# SCH_Senior_Transmitter_2026-04-05.net
KiCad netlist of a schematic drawn in EasyEDA
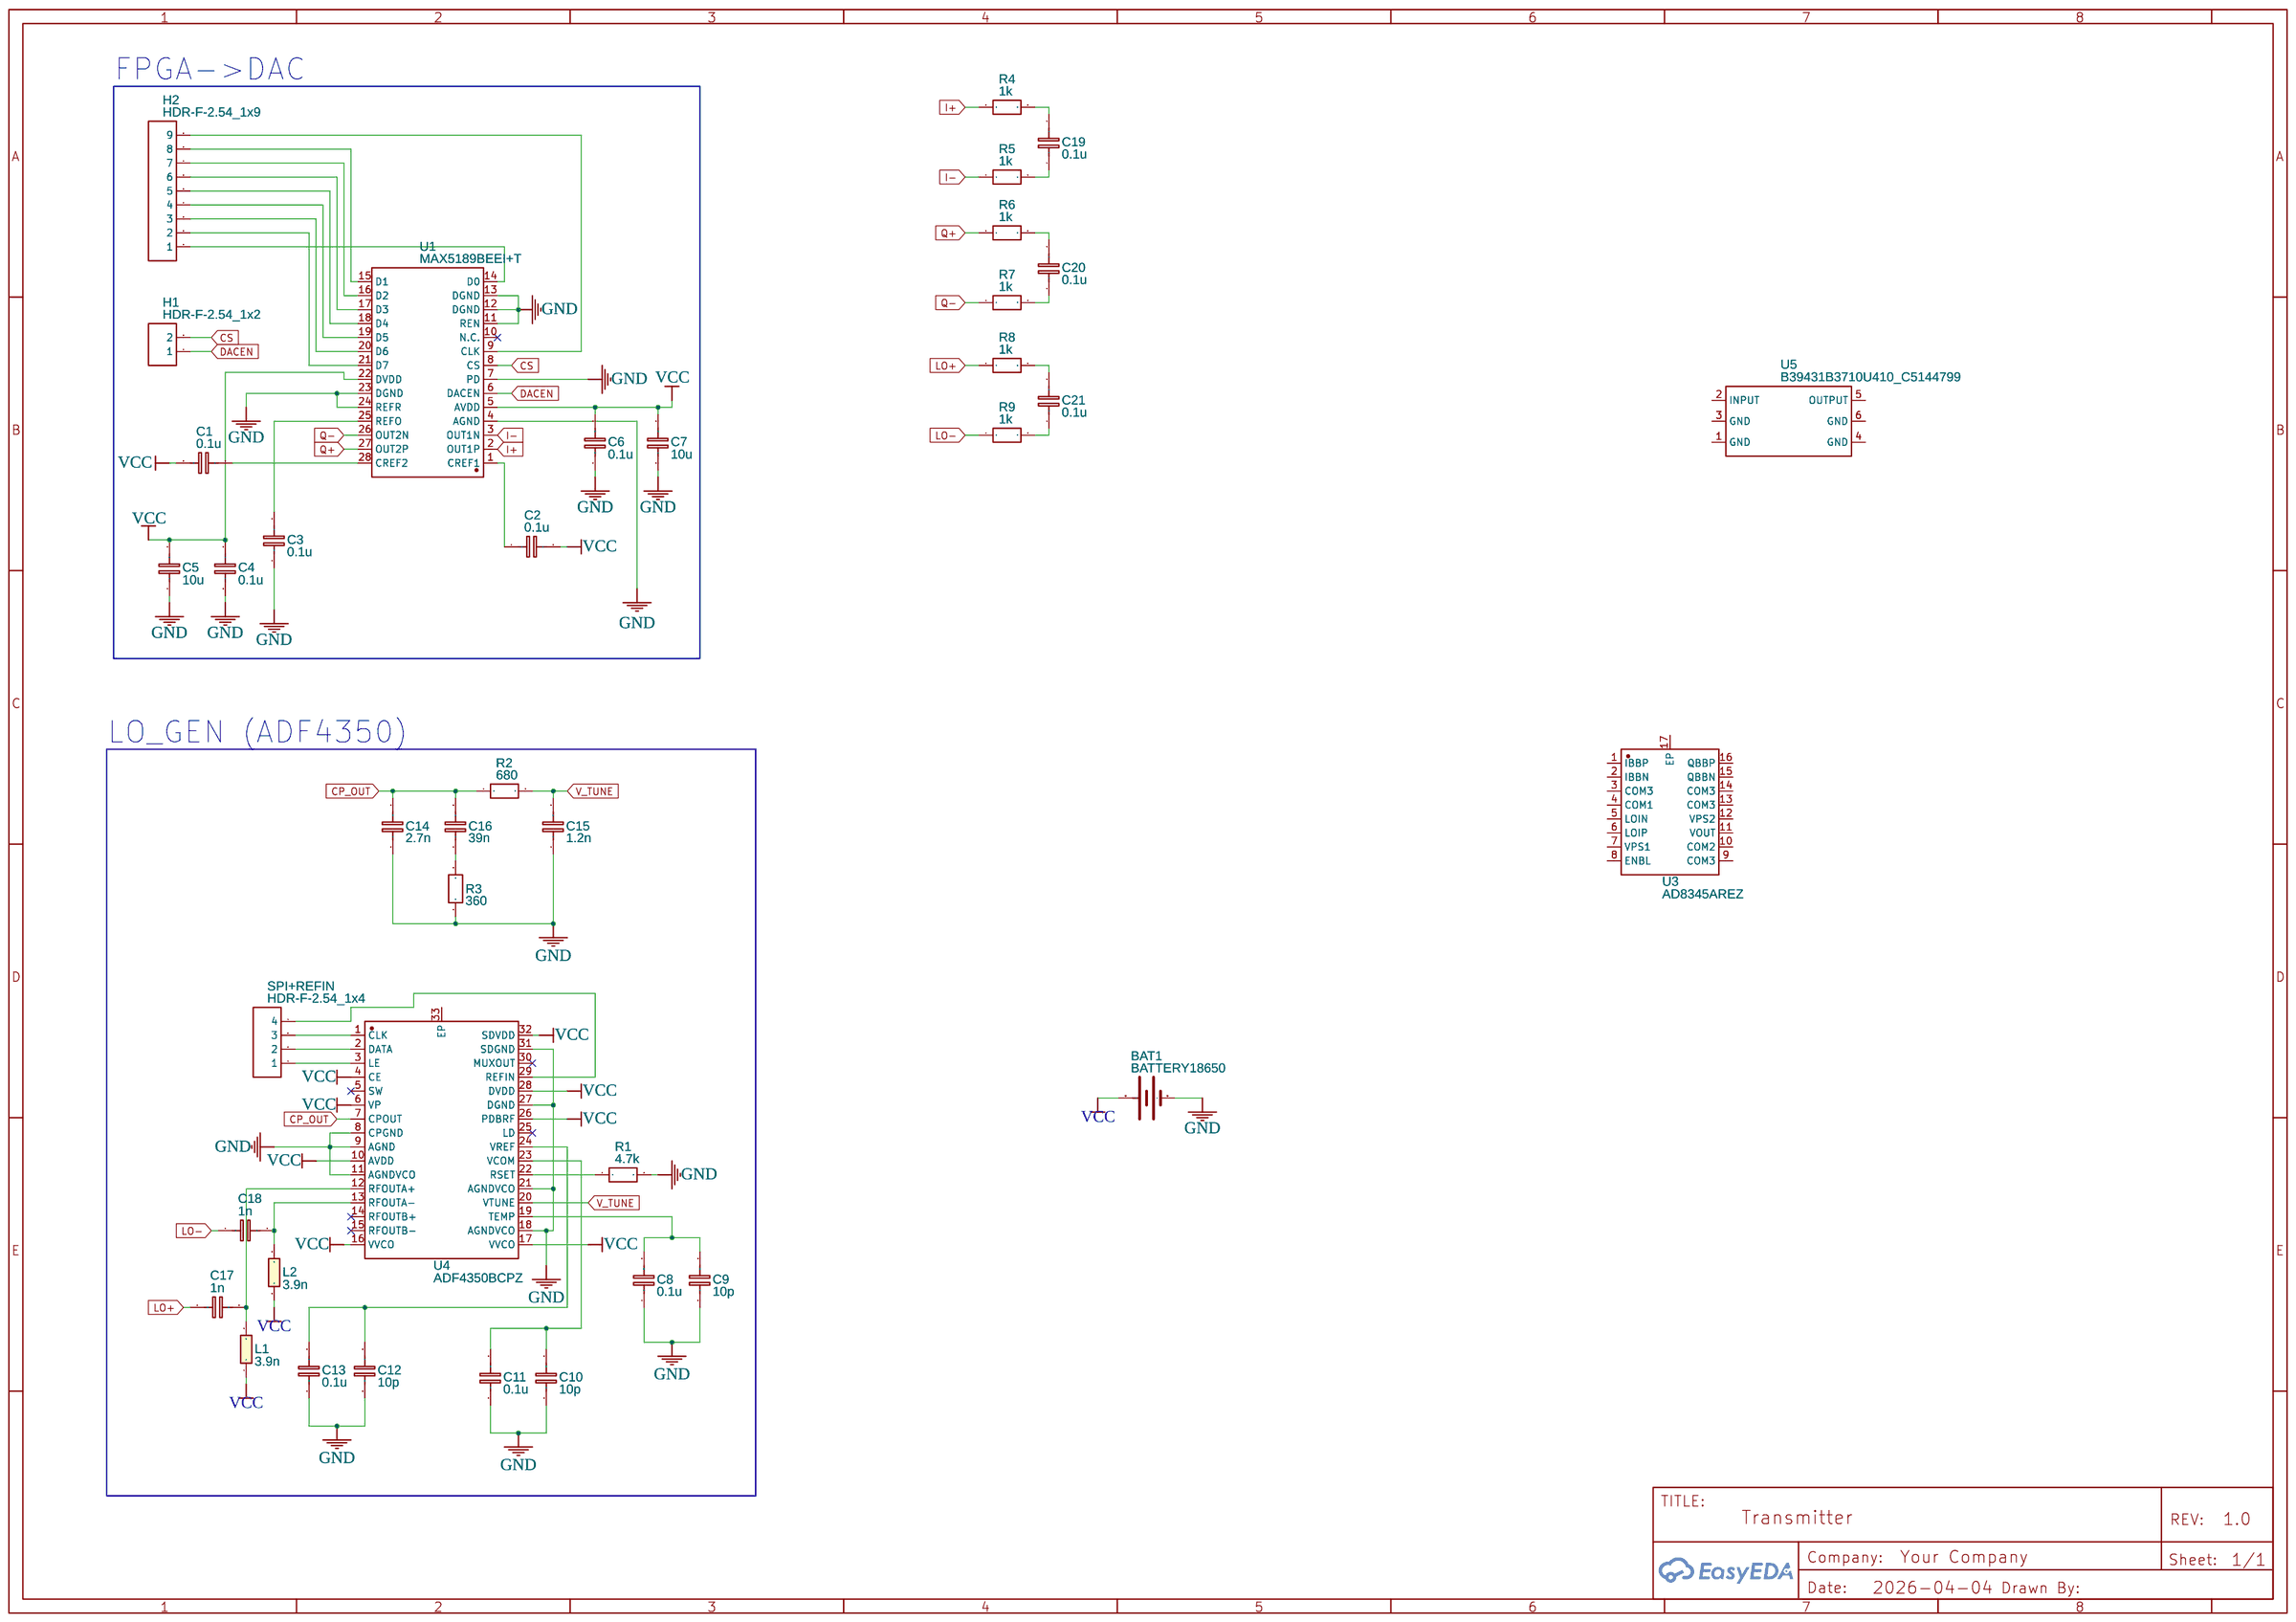
[diagram p0: schematic sheet]

(export (version "E")
  (design (tool "Eeschema 10.0.6"))
  (components
    (comp (ref "BAT1") (value "BATTERY18650") (libsource (lib "") (part "BATTERY18650")))
    (comp (ref "C1") (value "0.1u") (libsource (lib "") (part "C_0603_EU_3")))
    (comp (ref "C2") (value "0.1u") (libsource (lib "") (part "C_0603_EU_3")))
    (comp (ref "C3") (value "0.1u") (libsource (lib "") (part "C_0603_EU")))
    (comp (ref "C4") (value "0.1u") (libsource (lib "") (part "C_0603_EU")))
    (comp (ref "C5") (value "10u") (libsource (lib "") (part "C_0603_EU")))
    (comp (ref "C6") (value "0.1u") (libsource (lib "") (part "C_0603_EU_2")))
    (comp (ref "C7") (value "10u") (libsource (lib "") (part "C_0603_EU_2")))
    (comp (ref "C8") (value "0.1u") (libsource (lib "") (part "C_0603_EU_1")))
    (comp (ref "C9") (value "10p") (libsource (lib "") (part "C_0603_EU_1")))
    (comp (ref "C10") (value "10p") (libsource (lib "") (part "C_0603_EU_2")))
    (comp (ref "C11") (value "0.1u") (libsource (lib "") (part "C_0603_EU_2")))
    (comp (ref "C12") (value "10p") (libsource (lib "") (part "C_0603_EU_2")))
    (comp (ref "C13") (value "0.1u") (libsource (lib "") (part "C_0603_EU")))
    (comp (ref "C14") (value "2.7n") (libsource (lib "") (part "C_0603_EU_1")))
    (comp (ref "C15") (value "1.2n") (libsource (lib "") (part "C_0603_EU_1")))
    (comp (ref "C16") (value "39n") (libsource (lib "") (part "C_0603_EU_1")))
    (comp (ref "C17") (value "1n") (libsource (lib "") (part "C_0603_EU_3")))
    (comp (ref "C18") (value "1n") (libsource (lib "") (part "C_0603_EU_4")))
    (comp (ref "C19") (value "0.1u") (libsource (lib "") (part "C_0603_EU")))
    (comp (ref "C20") (value "0.1u") (libsource (lib "") (part "C_0603_EU")))
    (comp (ref "C21") (value "0.1u") (libsource (lib "") (part "C_0603_EU")))
    (comp (ref "H1") (value "HDR-F-2.54_1x2") (libsource (lib "") (part "HDR-F-2.54_1x2")))
    (comp (ref "H2") (value "HDR-F-2.54_1x9") (libsource (lib "") (part "HDR-F-2.54_1x9")))
    (comp (ref "L1") (value "3.9n") (libsource (lib "") (part "L0603_EU")))
    (comp (ref "L2") (value "3.9n") (libsource (lib "") (part "L0603_EU")))
    (comp (ref "R1") (value "4.7k") (libsource (lib "") (part "R_0603_EU")))
    (comp (ref "R2") (value "680") (libsource (lib "") (part "R_0603_EU")))
    (comp (ref "R3") (value "360") (libsource (lib "") (part "R_0603_EU_1")))
    (comp (ref "R4") (value "1k") (libsource (lib "") (part "R_0603_EU")))
    (comp (ref "R5") (value "1k") (libsource (lib "") (part "R_0603_EU")))
    (comp (ref "R6") (value "1k") (libsource (lib "") (part "R_0603_EU")))
    (comp (ref "R7") (value "1k") (libsource (lib "") (part "R_0603_EU")))
    (comp (ref "R8") (value "1k") (libsource (lib "") (part "R_0603_EU")))
    (comp (ref "R9") (value "1k") (libsource (lib "") (part "R_0603_EU")))
    (comp (ref "SPI+REFIN") (value "HDR-F-2.54_1x4") (libsource (lib "") (part "HDR-F-2.54_1x4")))
    (comp (ref "U1")
      (value "MAX5189BEEI+T")
      (fields (field (name "Manufacturer") "ADI(亚德诺)/MAXIM(美信)"))
      (libsource (lib "") (part "MAX5189BEEI+T"))
    )
    (comp (ref "U3")
      (value "AD8345AREZ")
      (fields (field (name "Manufacturer") "ADI(亚德诺)"))
      (libsource (lib "") (part "AD8345AREZ"))
    )
    (comp (ref "U4")
      (value "ADF4350BCPZ")
      (fields (field (name "Manufacturer") "ADI(亚德诺)"))
      (libsource (lib "") (part "ADF4350BCPZ"))
    )
    (comp (ref "U5")
      (value "B39431B3710U410_C5144799")
      (fields (field (name "Manufacturer Part") "B39431B3710U410"))
      (libsource (lib "") (part "B39431B3710U410_C5144799"))
    )
  )
  (nets
    (net (code "1") (name "CP_OUT") (class "Default")
      (node (ref "C14") (pin "2") (pinfunction "2_2") (pintype "unspecified"))
      (node (ref "C16") (pin "2") (pinfunction "2_2") (pintype "unspecified"))
      (node (ref "R2") (pin "1") (pinfunction "1_1") (pintype "unspecified"))
      (node (ref "U4") (pin "7") (pinfunction "CPOUT_7") (pintype "unspecified"))
    )
    (net (code "2") (name "CS") (class "Default")
      (node (ref "H1") (pin "2") (pinfunction "2_2") (pintype "input"))
      (node (ref "U1") (pin "8") (pinfunction "CS_8") (pintype "unspecified"))
    )
    (net (code "3") (name "DACEN") (class "Default")
      (node (ref "H1") (pin "1") (pinfunction "1_1") (pintype "input"))
      (node (ref "U1") (pin "6") (pinfunction "DACEN_6") (pintype "unspecified"))
    )
    (net (code "4") (name "GND") (class "Default")
      (node (ref "BAT1") (pin "GND@1") (pinfunction "-_GND@1") (pintype "passive"))
      (node (ref "C10") (pin "1") (pinfunction "1_1") (pintype "unspecified"))
      (node (ref "C11") (pin "1") (pinfunction "1_1") (pintype "unspecified"))
      (node (ref "C12") (pin "1") (pinfunction "1_1") (pintype "unspecified"))
      (node (ref "C13") (pin "1") (pinfunction "1_1") (pintype "unspecified"))
      (node (ref "C14") (pin "1") (pinfunction "1_1") (pintype "unspecified"))
      (node (ref "C15") (pin "1") (pinfunction "1_1") (pintype "unspecified"))
      (node (ref "C3") (pin "1") (pinfunction "1_1") (pintype "unspecified"))
      (node (ref "C4") (pin "1") (pinfunction "1_1") (pintype "unspecified"))
      (node (ref "C5") (pin "1") (pinfunction "1_1") (pintype "unspecified"))
      (node (ref "C6") (pin "1") (pinfunction "1_1") (pintype "unspecified"))
      (node (ref "C7") (pin "1") (pinfunction "1_1") (pintype "unspecified"))
      (node (ref "C8") (pin "1") (pinfunction "1_1") (pintype "unspecified"))
      (node (ref "C9") (pin "1") (pinfunction "1_1") (pintype "unspecified"))
      (node (ref "R1") (pin "2") (pinfunction "2_2") (pintype "unspecified"))
      (node (ref "R3") (pin "1") (pinfunction "1_1") (pintype "unspecified"))
      (node (ref "U1") (pin "11") (pinfunction "REN_11") (pintype "unspecified"))
      (node (ref "U1") (pin "12") (pinfunction "DGND_12") (pintype "unspecified"))
      (node (ref "U1") (pin "13") (pinfunction "DGND_13") (pintype "unspecified"))
      (node (ref "U1") (pin "23") (pinfunction "DGND_23") (pintype "unspecified"))
      (node (ref "U1") (pin "24") (pinfunction "REFR_24") (pintype "unspecified"))
      (node (ref "U1") (pin "4") (pinfunction "AGND_4") (pintype "unspecified"))
      (node (ref "U1") (pin "7") (pinfunction "PD_7") (pintype "unspecified"))
      (node (ref "U4") (pin "11") (pinfunction "AGNDVCO_11") (pintype "unspecified"))
      (node (ref "U4") (pin "18") (pinfunction "AGNDVCO_18") (pintype "unspecified"))
      (node (ref "U4") (pin "21") (pinfunction "AGNDVCO_21") (pintype "unspecified"))
      (node (ref "U4") (pin "27") (pinfunction "DGND_27") (pintype "unspecified"))
      (node (ref "U4") (pin "31") (pinfunction "SDGND_31") (pintype "unspecified"))
      (node (ref "U4") (pin "8") (pinfunction "CPGND_8") (pintype "unspecified"))
      (node (ref "U4") (pin "9") (pinfunction "AGND_9") (pintype "unspecified"))
    )
    (net (code "5") (name "I+") (class "Default")
      (node (ref "R4") (pin "1") (pinfunction "1_1") (pintype "unspecified"))
      (node (ref "U1") (pin "2") (pinfunction "OUT1P_2") (pintype "unspecified"))
    )
    (net (code "6") (name "I-") (class "Default")
      (node (ref "R5") (pin "1") (pinfunction "1_1") (pintype "unspecified"))
      (node (ref "U1") (pin "3") (pinfunction "OUT1N_3") (pintype "unspecified"))
    )
    (net (code "7") (name "LO+") (class "Default")
      (node (ref "C17") (pin "1") (pinfunction "1_1") (pintype "unspecified"))
      (node (ref "R8") (pin "1") (pinfunction "1_1") (pintype "unspecified"))
    )
    (net (code "8") (name "LO-") (class "Default")
      (node (ref "C18") (pin "1") (pinfunction "1_1") (pintype "unspecified"))
      (node (ref "R9") (pin "1") (pinfunction "1_1") (pintype "unspecified"))
    )
    (net (code "9") (name "Net-(C16-Pad1)") (class "Default")
      (node (ref "C16") (pin "1") (pinfunction "1_1") (pintype "unspecified"))
      (node (ref "R3") (pin "2") (pinfunction "2_2") (pintype "unspecified"))
    )
    (net (code "10") (name "Net-(C19-Pad1)") (class "Default")
      (node (ref "C19") (pin "1") (pinfunction "1_1") (pintype "unspecified"))
      (node (ref "R5") (pin "2") (pinfunction "2_2") (pintype "unspecified"))
    )
    (net (code "11") (name "Net-(C19-Pad2)") (class "Default")
      (node (ref "C19") (pin "2") (pinfunction "2_2") (pintype "unspecified"))
      (node (ref "R4") (pin "2") (pinfunction "2_2") (pintype "unspecified"))
    )
    (net (code "12") (name "Net-(C20-Pad1)") (class "Default")
      (node (ref "C20") (pin "1") (pinfunction "1_1") (pintype "unspecified"))
      (node (ref "R7") (pin "2") (pinfunction "2_2") (pintype "unspecified"))
    )
    (net (code "13") (name "Net-(C20-Pad2)") (class "Default")
      (node (ref "C20") (pin "2") (pinfunction "2_2") (pintype "unspecified"))
      (node (ref "R6") (pin "2") (pinfunction "2_2") (pintype "unspecified"))
    )
    (net (code "14") (name "Net-(C21-Pad1)") (class "Default")
      (node (ref "C21") (pin "1") (pinfunction "1_1") (pintype "unspecified"))
      (node (ref "R9") (pin "2") (pinfunction "2_2") (pintype "unspecified"))
    )
    (net (code "15") (name "Net-(C21-Pad2)") (class "Default")
      (node (ref "C21") (pin "2") (pinfunction "2_2") (pintype "unspecified"))
      (node (ref "R8") (pin "2") (pinfunction "2_2") (pintype "unspecified"))
    )
    (net (code "16") (name "Net-(U1-CLK)") (class "Default")
      (node (ref "H2") (pin "9") (pinfunction "9_9") (pintype "unspecified"))
      (node (ref "U1") (pin "9") (pinfunction "CLK_9") (pintype "unspecified"))
    )
    (net (code "17") (name "Net-(U1-CREF1)") (class "Default")
      (node (ref "C2") (pin "1") (pinfunction "1_1") (pintype "unspecified"))
      (node (ref "U1") (pin "1") (pinfunction "CREF1_1") (pintype "unspecified"))
    )
    (net (code "18") (name "Net-(U1-CREF2)") (class "Default")
      (node (ref "C1") (pin "2") (pinfunction "2_2") (pintype "unspecified"))
      (node (ref "U1") (pin "28") (pinfunction "CREF2_28") (pintype "unspecified"))
    )
    (net (code "19") (name "Net-(U1-D0)") (class "Default")
      (node (ref "H2") (pin "1") (pinfunction "1_1") (pintype "unspecified"))
      (node (ref "U1") (pin "14") (pinfunction "D0_14") (pintype "unspecified"))
    )
    (net (code "20") (name "Net-(U1-D1)") (class "Default")
      (node (ref "H2") (pin "8") (pinfunction "8_8") (pintype "unspecified"))
      (node (ref "U1") (pin "15") (pinfunction "D1_15") (pintype "unspecified"))
    )
    (net (code "21") (name "Net-(U1-D2)") (class "Default")
      (node (ref "H2") (pin "7") (pinfunction "7_7") (pintype "unspecified"))
      (node (ref "U1") (pin "16") (pinfunction "D2_16") (pintype "unspecified"))
    )
    (net (code "22") (name "Net-(U1-D3)") (class "Default")
      (node (ref "H2") (pin "6") (pinfunction "6_6") (pintype "unspecified"))
      (node (ref "U1") (pin "17") (pinfunction "D3_17") (pintype "unspecified"))
    )
    (net (code "23") (name "Net-(U1-D4)") (class "Default")
      (node (ref "H2") (pin "5") (pinfunction "5_5") (pintype "unspecified"))
      (node (ref "U1") (pin "18") (pinfunction "D4_18") (pintype "unspecified"))
    )
    (net (code "24") (name "Net-(U1-D5)") (class "Default")
      (node (ref "H2") (pin "4") (pinfunction "4_4") (pintype "unspecified"))
      (node (ref "U1") (pin "19") (pinfunction "D5_19") (pintype "unspecified"))
    )
    (net (code "25") (name "Net-(U1-D6)") (class "Default")
      (node (ref "H2") (pin "3") (pinfunction "3_3") (pintype "unspecified"))
      (node (ref "U1") (pin "20") (pinfunction "D6_20") (pintype "unspecified"))
    )
    (net (code "26") (name "Net-(U1-D7)") (class "Default")
      (node (ref "H2") (pin "2") (pinfunction "2_2") (pintype "unspecified"))
      (node (ref "U1") (pin "21") (pinfunction "D7_21") (pintype "unspecified"))
    )
    (net (code "27") (name "Net-(U1-REFO)") (class "Default")
      (node (ref "C3") (pin "2") (pinfunction "2_2") (pintype "unspecified"))
      (node (ref "U1") (pin "25") (pinfunction "REFO_25") (pintype "unspecified"))
    )
    (net (code "28") (name "Net-(U4-CLK)") (class "Default")
      (node (ref "SPI+REFIN") (pin "3") (pinfunction "3_3") (pintype "unspecified"))
      (node (ref "U4") (pin "1") (pinfunction "CLK_1") (pintype "unspecified"))
    )
    (net (code "29") (name "Net-(U4-DATA)") (class "Default")
      (node (ref "SPI+REFIN") (pin "2") (pinfunction "2_2") (pintype "unspecified"))
      (node (ref "U4") (pin "2") (pinfunction "DATA_2") (pintype "unspecified"))
    )
    (net (code "30") (name "Net-(U4-LE)") (class "Default")
      (node (ref "SPI+REFIN") (pin "1") (pinfunction "1_1") (pintype "unspecified"))
      (node (ref "U4") (pin "3") (pinfunction "LE_3") (pintype "unspecified"))
    )
    (net (code "31") (name "Net-(U4-REFIN)") (class "Default")
      (node (ref "SPI+REFIN") (pin "4") (pinfunction "4_4") (pintype "unspecified"))
      (node (ref "U4") (pin "29") (pinfunction "REFIN_29") (pintype "unspecified"))
    )
    (net (code "32") (name "Net-(U4-RFOUTA+)") (class "Default")
      (node (ref "C17") (pin "2") (pinfunction "2_2") (pintype "unspecified"))
      (node (ref "L1") (pin "2") (pinfunction "2_2") (pintype "unspecified"))
      (node (ref "U4") (pin "12") (pinfunction "RFOUTA+_12") (pintype "unspecified"))
    )
    (net (code "33") (name "Net-(U4-RFOUTA-)") (class "Default")
      (node (ref "C18") (pin "2") (pinfunction "2_2") (pintype "unspecified"))
      (node (ref "L2") (pin "2") (pinfunction "2_2") (pintype "unspecified"))
      (node (ref "U4") (pin "13") (pinfunction "RFOUTA-_13") (pintype "unspecified"))
    )
    (net (code "34") (name "Net-(U4-RSET)") (class "Default")
      (node (ref "R1") (pin "1") (pinfunction "1_1") (pintype "unspecified"))
      (node (ref "U4") (pin "22") (pinfunction "RSET_22") (pintype "unspecified"))
    )
    (net (code "35") (name "Net-(U4-TEMP)") (class "Default")
      (node (ref "C8") (pin "2") (pinfunction "2_2") (pintype "unspecified"))
      (node (ref "C9") (pin "2") (pinfunction "2_2") (pintype "unspecified"))
      (node (ref "U4") (pin "19") (pinfunction "TEMP_19") (pintype "unspecified"))
    )
    (net (code "36") (name "Net-(U4-VCOM)") (class "Default")
      (node (ref "C10") (pin "2") (pinfunction "2_2") (pintype "unspecified"))
      (node (ref "C11") (pin "2") (pinfunction "2_2") (pintype "unspecified"))
      (node (ref "U4") (pin "23") (pinfunction "VCOM_23") (pintype "unspecified"))
    )
    (net (code "37") (name "Net-(U4-VREF)") (class "Default")
      (node (ref "C12") (pin "2") (pinfunction "2_2") (pintype "unspecified"))
      (node (ref "C13") (pin "2") (pinfunction "2_2") (pintype "unspecified"))
      (node (ref "U4") (pin "24") (pinfunction "VREF_24") (pintype "unspecified"))
    )
    (net (code "38") (name "Q+") (class "Default")
      (node (ref "R6") (pin "1") (pinfunction "1_1") (pintype "unspecified"))
      (node (ref "U1") (pin "27") (pinfunction "OUT2P_27") (pintype "unspecified"))
    )
    (net (code "39") (name "Q-") (class "Default")
      (node (ref "R7") (pin "1") (pinfunction "1_1") (pintype "unspecified"))
      (node (ref "U1") (pin "26") (pinfunction "OUT2N_26") (pintype "unspecified"))
    )
    (net (code "40") (name "VCC") (class "Default")
      (node (ref "BAT1") (pin "PWR@1") (pinfunction "+_PWR@1") (pintype "passive"))
      (node (ref "C1") (pin "1") (pinfunction "1_1") (pintype "unspecified"))
      (node (ref "C2") (pin "2") (pinfunction "2_2") (pintype "unspecified"))
      (node (ref "C4") (pin "2") (pinfunction "2_2") (pintype "unspecified"))
      (node (ref "C5") (pin "2") (pinfunction "2_2") (pintype "unspecified"))
      (node (ref "C6") (pin "2") (pinfunction "2_2") (pintype "unspecified"))
      (node (ref "C7") (pin "2") (pinfunction "2_2") (pintype "unspecified"))
      (node (ref "L1") (pin "1") (pinfunction "1_1") (pintype "unspecified"))
      (node (ref "L2") (pin "1") (pinfunction "1_1") (pintype "unspecified"))
      (node (ref "U1") (pin "22") (pinfunction "DVDD_22") (pintype "unspecified"))
      (node (ref "U1") (pin "5") (pinfunction "AVDD_5") (pintype "unspecified"))
      (node (ref "U4") (pin "10") (pinfunction "AVDD_10") (pintype "unspecified"))
      (node (ref "U4") (pin "16") (pinfunction "VVCO_16") (pintype "unspecified"))
      (node (ref "U4") (pin "17") (pinfunction "VVCO_17") (pintype "unspecified"))
      (node (ref "U4") (pin "26") (pinfunction "PDBRF_26") (pintype "unspecified"))
      (node (ref "U4") (pin "28") (pinfunction "DVDD_28") (pintype "unspecified"))
      (node (ref "U4") (pin "32") (pinfunction "SDVDD_32") (pintype "unspecified"))
      (node (ref "U4") (pin "4") (pinfunction "CE_4") (pintype "unspecified"))
      (node (ref "U4") (pin "6") (pinfunction "VP_6") (pintype "unspecified"))
    )
    (net (code "41") (name "V_TUNE") (class "Default")
      (node (ref "C15") (pin "2") (pinfunction "2_2") (pintype "unspecified"))
      (node (ref "R2") (pin "2") (pinfunction "2_2") (pintype "unspecified"))
      (node (ref "U4") (pin "20") (pinfunction "VTUNE_20") (pintype "unspecified"))
    )
    (net (code "42") (name "unconnected-(U1-N.C.-Pad10)") (class "Default")
      (node (ref "U1") (pin "10") (pinfunction "N.C._10") (pintype "unspecified+no_connect"))
    )
    (net (code "43") (name "unconnected-(U3-COM1-Pad4)") (class "Default")
      (node (ref "U3") (pin "4") (pinfunction "COM1_4") (pintype "unspecified"))
    )
    (net (code "44") (name "unconnected-(U3-COM2-Pad10)") (class "Default")
      (node (ref "U3") (pin "10") (pinfunction "COM2_10") (pintype "unspecified"))
    )
    (net (code "45") (name "unconnected-(U3-COM3-Pad3)") (class "Default")
      (node (ref "U3") (pin "3") (pinfunction "COM3_3") (pintype "unspecified"))
    )
    (net (code "46") (name "unconnected-(U3-COM3-Pad9)") (class "Default")
      (node (ref "U3") (pin "9") (pinfunction "COM3_9") (pintype "unspecified"))
    )
    (net (code "47") (name "unconnected-(U3-COM3-Pad13)") (class "Default")
      (node (ref "U3") (pin "13") (pinfunction "COM3_13") (pintype "unspecified"))
    )
    (net (code "48") (name "unconnected-(U3-COM3-Pad14)") (class "Default")
      (node (ref "U3") (pin "14") (pinfunction "COM3_14") (pintype "unspecified"))
    )
    (net (code "49") (name "unconnected-(U3-ENBL-Pad8)") (class "Default")
      (node (ref "U3") (pin "8") (pinfunction "ENBL_8") (pintype "unspecified"))
    )
    (net (code "50") (name "unconnected-(U3-EP-Pad17)") (class "Default")
      (node (ref "U3") (pin "17") (pinfunction "EP_17") (pintype "unspecified"))
    )
    (net (code "51") (name "unconnected-(U3-IBBN-Pad2)") (class "Default")
      (node (ref "U3") (pin "2") (pinfunction "IBBN_2") (pintype "unspecified"))
    )
    (net (code "52") (name "unconnected-(U3-IBBP-Pad1)") (class "Default")
      (node (ref "U3") (pin "1") (pinfunction "IBBP_1") (pintype "unspecified"))
    )
    (net (code "53") (name "unconnected-(U3-LOIN-Pad5)") (class "Default")
      (node (ref "U3") (pin "5") (pinfunction "LOIN_5") (pintype "unspecified"))
    )
    (net (code "54") (name "unconnected-(U3-LOIP-Pad6)") (class "Default")
      (node (ref "U3") (pin "6") (pinfunction "LOIP_6") (pintype "unspecified"))
    )
    (net (code "55") (name "unconnected-(U3-QBBN-Pad15)") (class "Default")
      (node (ref "U3") (pin "15") (pinfunction "QBBN_15") (pintype "unspecified"))
    )
    (net (code "56") (name "unconnected-(U3-QBBP-Pad16)") (class "Default")
      (node (ref "U3") (pin "16") (pinfunction "QBBP_16") (pintype "unspecified"))
    )
    (net (code "57") (name "unconnected-(U3-VOUT-Pad11)") (class "Default")
      (node (ref "U3") (pin "11") (pinfunction "VOUT_11") (pintype "unspecified"))
    )
    (net (code "58") (name "unconnected-(U3-VPS1-Pad7)") (class "Default")
      (node (ref "U3") (pin "7") (pinfunction "VPS1_7") (pintype "unspecified"))
    )
    (net (code "59") (name "unconnected-(U3-VPS2-Pad12)") (class "Default")
      (node (ref "U3") (pin "12") (pinfunction "VPS2_12") (pintype "unspecified"))
    )
    (net (code "60") (name "unconnected-(U4-EP-Pad33)") (class "Default")
      (node (ref "U4") (pin "33") (pinfunction "EP_33") (pintype "unspecified"))
    )
    (net (code "61") (name "unconnected-(U4-LD-Pad25)") (class "Default")
      (node (ref "U4") (pin "25") (pinfunction "LD_25") (pintype "unspecified+no_connect"))
    )
    (net (code "62") (name "unconnected-(U4-MUXOUT-Pad30)") (class "Default")
      (node (ref "U4") (pin "30") (pinfunction "MUXOUT_30") (pintype "unspecified+no_connect"))
    )
    (net (code "63") (name "unconnected-(U4-RFOUTB+-Pad14)") (class "Default")
      (node (ref "U4") (pin "14") (pinfunction "RFOUTB+_14") (pintype "unspecified+no_connect"))
    )
    (net (code "64") (name "unconnected-(U4-RFOUTB--Pad15)") (class "Default")
      (node (ref "U4") (pin "15") (pinfunction "RFOUTB-_15") (pintype "unspecified+no_connect"))
    )
    (net (code "65") (name "unconnected-(U4-SW-Pad5)") (class "Default")
      (node (ref "U4") (pin "5") (pinfunction "SW_5") (pintype "unspecified+no_connect"))
    )
    (net (code "66") (name "unconnected-(U5-GND-Pad1)") (class "Default")
      (node (ref "U5") (pin "1") (pinfunction "GND_1") (pintype "unspecified"))
    )
    (net (code "67") (name "unconnected-(U5-GND-Pad3)") (class "Default")
      (node (ref "U5") (pin "3") (pinfunction "GND_3") (pintype "unspecified"))
    )
    (net (code "68") (name "unconnected-(U5-GND-Pad4)") (class "Default")
      (node (ref "U5") (pin "4") (pinfunction "GND_4") (pintype "unspecified"))
    )
    (net (code "69") (name "unconnected-(U5-GND-Pad6)") (class "Default")
      (node (ref "U5") (pin "6") (pinfunction "GND_6") (pintype "unspecified"))
    )
    (net (code "70") (name "unconnected-(U5-INPUT-Pad2)") (class "Default")
      (node (ref "U5") (pin "2") (pinfunction "INPUT_2") (pintype "unspecified"))
    )
    (net (code "71") (name "unconnected-(U5-OUTPUT-Pad5)") (class "Default")
      (node (ref "U5") (pin "5") (pinfunction "OUTPUT_5") (pintype "unspecified"))
    )
  )
)
